# 40_Flash-eMMC_Flash.net
KiCad netlist of a schematic drawn in Altium Designer
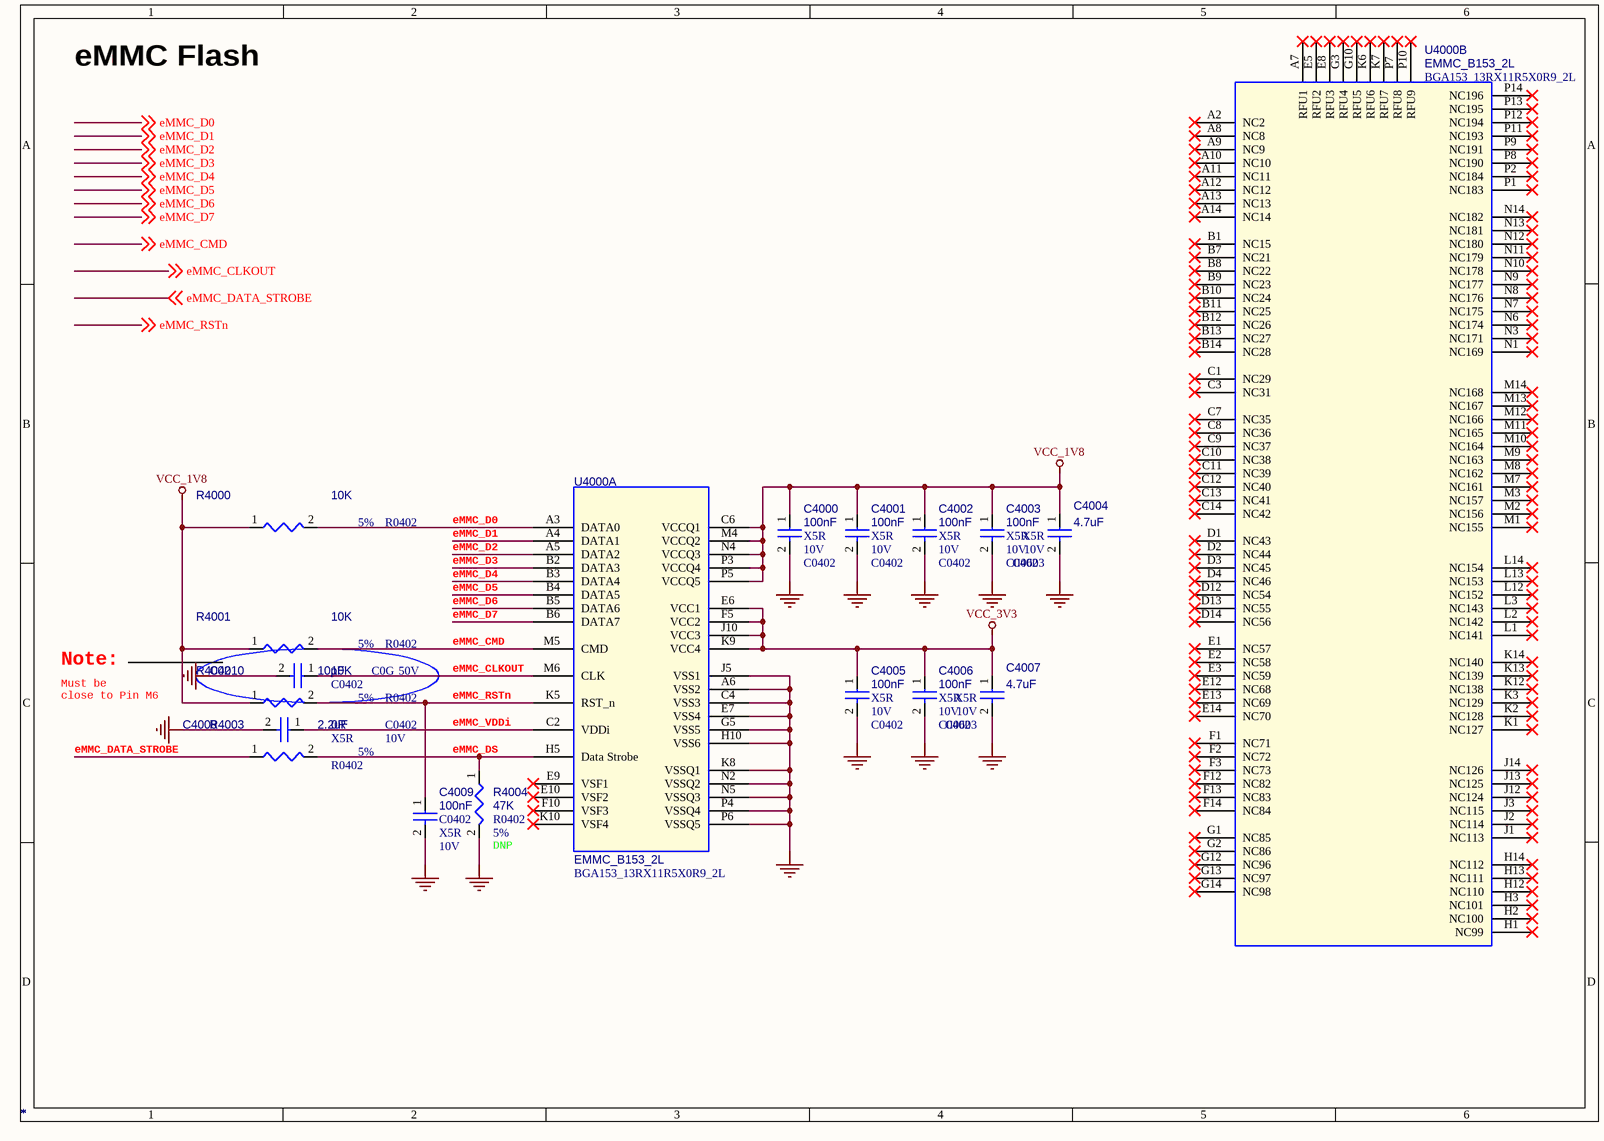
[diagram p0: 40.Flash-eMMC Flash.SchDoc]

(export (version "E")
  (design (tool "Eeschema 10.0.6"))
  (components
    (comp (ref "C4000")
      (value "*")
      (footprint "C0402")
      (description "cap,100.00nF,+/-10%,10V,X5R,C0402")
      (fields
        (field (name "VOLTAGE") "10V")
        (field (name "PCB FOOTPRINT") "C0402")
        (field (name "DIELECTRIC") "X5R")
        (field (name "TOLERANCE") "10%")
        (field (name "MANUFACTURER") "TDK")
        (field (name "ALTIUM_UNNAMED_1") "100nF")
        (field (name "CREATED BY") "JJJ")
      )
      (libsource (lib "*") (part "CAP NP"))
    )
    (comp (ref "C4001")
      (value "*")
      (footprint "C0402")
      (description "cap,100.00nF,+/-10%,10V,X5R,C0402")
      (fields
        (field (name "VOLTAGE") "10V")
        (field (name "PCB FOOTPRINT") "C0402")
        (field (name "DIELECTRIC") "X5R")
        (field (name "MANUFACTURER") "TDK")
        (field (name "TOLERANCE") "10%")
        (field (name "ALTIUM_UNNAMED_1") "100nF")
        (field (name "CREATED BY") "JJJ")
      )
      (libsource (lib "*") (part "CAP NP"))
    )
    (comp (ref "C4002")
      (value "*")
      (footprint "C0402")
      (description "cap,100.00nF,+/-10%,10V,X5R,C0402")
      (fields
        (field (name "VOLTAGE") "10V")
        (field (name "PCB FOOTPRINT") "C0402")
        (field (name "DIELECTRIC") "X5R")
        (field (name "MANUFACTURER") "TDK")
        (field (name "TOLERANCE") "10%")
        (field (name "ALTIUM_UNNAMED_1") "100nF")
        (field (name "CREATED BY") "JJJ")
      )
      (libsource (lib "*") (part "CAP NP"))
    )
    (comp (ref "C4003")
      (value "*")
      (footprint "C0402")
      (description "cap,100.00nF,+/-10%,10V,X5R,C0402")
      (fields
        (field (name "VOLTAGE") "10V")
        (field (name "PCB FOOTPRINT") "C0402")
        (field (name "DIELECTRIC") "X5R")
        (field (name "TOLERANCE") "10%")
        (field (name "MANUFACTURER") "TDK")
        (field (name "ALTIUM_UNNAMED_1") "100nF")
        (field (name "CREATED BY") "JJJ")
      )
      (libsource (lib "*") (part "CAP NP"))
    )
    (comp (ref "C4004")
      (value "*")
      (footprint "C0603")
      (description "cap,4.70uF,+/-10%,10V,X5R,C0603")
      (fields
        (field (name "VOLTAGE") "10V")
        (field (name "PCB FOOTPRINT") "C0603")
        (field (name "DIELECTRIC") "X5R")
        (field (name "TOLERANCE") "10%")
        (field (name "MANUFACTURER") "TDK")
        (field (name "ALTIUM_UNNAMED_1") "4.7uF")
        (field (name "CREATED BY") "JJJ")
      )
      (libsource (lib "*") (part "CAP NP"))
    )
    (comp (ref "C4005")
      (value "*")
      (footprint "C0402")
      (description "cap,100.00nF,+/-10%,10V,X5R,C0402")
      (fields
        (field (name "VOLTAGE") "10V")
        (field (name "PCB FOOTPRINT") "C0402")
        (field (name "DIELECTRIC") "X5R")
        (field (name "MANUFACTURER") "TDK")
        (field (name "TOLERANCE") "10%")
        (field (name "ALTIUM_UNNAMED_1") "100nF")
        (field (name "CREATED BY") "JJJ")
      )
      (libsource (lib "*") (part "CAP NP"))
    )
    (comp (ref "C4006")
      (value "*")
      (footprint "C0402")
      (description "cap,100.00nF,+/-10%,10V,X5R,C0402")
      (fields
        (field (name "VOLTAGE") "10V")
        (field (name "PCB FOOTPRINT") "C0402")
        (field (name "DIELECTRIC") "X5R")
        (field (name "MANUFACTURER") "TDK")
        (field (name "TOLERANCE") "10%")
        (field (name "ALTIUM_UNNAMED_1") "100nF")
        (field (name "CREATED BY") "JJJ")
      )
      (libsource (lib "*") (part "CAP NP"))
    )
    (comp (ref "C4007")
      (value "*")
      (footprint "C0603")
      (description "cap,4.70uF,+/-10%,10V,X5R,C0603")
      (fields
        (field (name "VOLTAGE") "10V")
        (field (name "PCB FOOTPRINT") "C0603")
        (field (name "DIELECTRIC") "X5R")
        (field (name "TOLERANCE") "10%")
        (field (name "MANUFACTURER") "TDK")
        (field (name "ALTIUM_UNNAMED_1") "4.7uF")
        (field (name "CREATED BY") "JJJ")
      )
      (libsource (lib "*") (part "CAP NP"))
    )
    (comp (ref "C4008")
      (value "*")
      (footprint "C0402")
      (description "cap,2.20uF,+/-10%,10V,X5R,C0402")
      (fields
        (field (name "VOLTAGE") "10V")
        (field (name "PCB FOOTPRINT") "C0402")
        (field (name "DIELECTRIC") "X5R")
        (field (name "TOLERANCE") "10%")
        (field (name "MANUFACTURER") "TDK")
        (field (name "ALTIUM_UNNAMED_1") "2.2uF")
        (field (name "CREATED BY") "JJJ")
      )
      (libsource (lib "*") (part "CAP NP"))
    )
    (comp (ref "C4009")
      (value "*")
      (footprint "C0402")
      (description "cap,100.00nF,+/-10%,10V,X5R,C0402")
      (fields
        (field (name "VOLTAGE") "10V")
        (field (name "PCB FOOTPRINT") "C0402")
        (field (name "DIELECTRIC") "X5R")
        (field (name "TOLERANCE") "10%")
        (field (name "MANUFACTURER") "TDK")
        (field (name "ALTIUM_UNNAMED_1") "100nF")
        (field (name "CREATED BY") "JJJ")
      )
      (libsource (lib "*") (part "CAP NP"))
    )
    (comp (ref "C4010")
      (value "*")
      (footprint "C0402")
      (description "cap,10.00pF,+/-0.5,50V,C0G,C0402")
      (fields
        (field (name "VOLTAGE") "50V")
        (field (name "PCB FOOTPRINT") "C0402")
        (field (name "DIELECTRIC") "C0G")
        (field (name "TOLERANCE") "+/-0.5pF")
        (field (name "MANUFACTURER") "TDK")
        (field (name "ALTIUM_UNNAMED_1") "10pF")
        (field (name "CREATED BY") "JJJ")
      )
      (libsource (lib "*") (part "CAP NP"))
    )
    (comp (ref "R4000")
      (value "*")
      (footprint "R0402")
      (description "НЁУГєсД¤µзЧи,10K,+/-5%,R0402,1/16W.")
      (fields
        (field (name "PCB FOOTPRINT") "R0402")
        (field (name "TOLERANCE") "5%")
        (field (name "MANUFACTURER") "YAGEO")
        (field (name "ALTIUM_UNNAMED_1") "10K")
        (field (name "CREATED BY") "YTL")
      )
      (libsource (lib "*") (part "RESISTOR_Dup1"))
    )
    (comp (ref "R4001")
      (value "*")
      (footprint "R0402")
      (description "НЁУГєсД¤µзЧи,10K,+/-5%,R0402,1/16W.")
      (fields
        (field (name "PCB FOOTPRINT") "R0402")
        (field (name "TOLERANCE") "5%")
        (field (name "MANUFACTURER") "YAGEO")
        (field (name "ALTIUM_UNNAMED_1") "10K")
        (field (name "CREATED BY") "YTL")
      )
      (libsource (lib "*") (part "RESISTOR_Dup1"))
    )
    (comp (ref "R4002")
      (value "*")
      (footprint "R0402")
      (description "НЁУГєсД¤µзЧи,10K,+/-5%,R0402,1/16W.")
      (fields
        (field (name "PCB FOOTPRINT") "R0402")
        (field (name "TOLERANCE") "5%")
        (field (name "MANUFACTURER") "YAGEO")
        (field (name "ALTIUM_UNNAMED_1") "10K")
        (field (name "CREATED BY") "YTL")
      )
      (libsource (lib "*") (part "RESISTOR_Dup1"))
    )
    (comp (ref "R4003")
      (value "*")
      (footprint "R0402")
      (description "НЁУГєсД¤µзЧи,0R,+/-5%,R0402,1/16W.")
      (fields
        (field (name "PCB FOOTPRINT") "R0402")
        (field (name "TOLERANCE") "5%")
        (field (name "MANUFACTURER") "YAGEO")
        (field (name "ALTIUM_UNNAMED_1") "0R")
        (field (name "CREATED BY") "YTL")
      )
      (libsource (lib "*") (part "RESISTOR_Dup1"))
    )
    (comp (ref "R4004")
      (value "*")
      (footprint "R0402")
      (description "НЁУГєсД¤µзЧи,47K,+/-5%,R0402,1/16W.")
      (fields
        (field (name "PCB FOOTPRINT") "R0402")
        (field (name "TOLERANCE") "5%")
        (field (name "MANUFACTURER") "YAGEO")
        (field (name "OPTION") "DNP")
        (field (name "ALTIUM_UNNAMED_1") "47K")
        (field (name "CREATED BY") "YTL")
      )
      (libsource (lib "*") (part "RESISTOR_Dup1"))
    )
    (comp (ref "U4000")
      (value "*")
      (footprint "BGA153_13RX11R5X0R9_2L")
      (description "EMMC_B153_2L,ёьєГµДВъЧг№¤ТХРиЗуЈ¬Fanout·ЅКЅІї·ЦЧЯПЯїзЅУФЩЗтО»ЙПЈ¬НЪіэA1\\C5ЗтО»")
      (fields
        (field (name "PCB FOOTPRINT") "BGA153_13RX11R5X0R9_2L")
        (field (name "ALTIUM_UNNAMED_1") "EMMC_B153_2L")
        (field (name "CREATED BY") "YWQ")
      )
      (libsource (lib "*") (part "INAND_EMMC_153_2L"))
    )
  )
  (nets
    (net (code "1") (name "/eMMC_DS") (class "Default")
      (node (ref "R4003") (pin "2") (pinfunction "2_2") (pintype "passive"))
      (node (ref "R4004") (pin "1") (pinfunction "1_1") (pintype "passive"))
      (node (ref "U4000") (pin "H5") (pinfunction "Data_Strobe_H5") (pintype "passive"))
    )
    (net (code "2") (name "/eMMC_VDDi") (class "Default")
      (node (ref "C4008") (pin "1") (pinfunction "1_1") (pintype "passive"))
      (node (ref "U4000") (pin "C2") (pinfunction "VDDi_C2") (pintype "passive"))
    )
    (net (code "3") (name "GND") (class "Default")
      (node (ref "C4000") (pin "2") (pinfunction "2_2") (pintype "passive"))
      (node (ref "C4001") (pin "2") (pinfunction "2_2") (pintype "passive"))
      (node (ref "C4002") (pin "2") (pinfunction "2_2") (pintype "passive"))
      (node (ref "C4003") (pin "2") (pinfunction "2_2") (pintype "passive"))
      (node (ref "C4004") (pin "2") (pinfunction "2_2") (pintype "passive"))
      (node (ref "C4005") (pin "2") (pinfunction "2_2") (pintype "passive"))
      (node (ref "C4006") (pin "2") (pinfunction "2_2") (pintype "passive"))
      (node (ref "C4007") (pin "2") (pinfunction "2_2") (pintype "passive"))
      (node (ref "C4008") (pin "2") (pinfunction "2_2") (pintype "passive"))
      (node (ref "C4009") (pin "2") (pinfunction "2_2") (pintype "passive"))
      (node (ref "C4010") (pin "2") (pinfunction "2_2") (pintype "passive"))
      (node (ref "R4004") (pin "2") (pinfunction "2_2") (pintype "passive"))
      (node (ref "U4000") (pin "A6") (pinfunction "VSS2_A6") (pintype "passive"))
      (node (ref "U4000") (pin "C4") (pinfunction "VSS3_C4") (pintype "passive"))
      (node (ref "U4000") (pin "E7") (pinfunction "VSS4_E7") (pintype "passive"))
      (node (ref "U4000") (pin "G5") (pinfunction "VSS5_G5") (pintype "passive"))
      (node (ref "U4000") (pin "H10") (pinfunction "VSS6_H10") (pintype "passive"))
      (node (ref "U4000") (pin "J5") (pinfunction "VSS1_J5") (pintype "passive"))
      (node (ref "U4000") (pin "K8") (pinfunction "VSSQ1_K8") (pintype "passive"))
      (node (ref "U4000") (pin "N2") (pinfunction "VSSQ2_N2") (pintype "passive"))
      (node (ref "U4000") (pin "N5") (pinfunction "VSSQ3_N5") (pintype "passive"))
      (node (ref "U4000") (pin "P4") (pinfunction "VSSQ4_P4") (pintype "passive"))
      (node (ref "U4000") (pin "P6") (pinfunction "VSSQ5_P6") (pintype "passive"))
    )
    (net (code "4") (name "VCC_1V8") (class "Default")
      (node (ref "C4000") (pin "1") (pinfunction "1_1") (pintype "passive"))
      (node (ref "C4001") (pin "1") (pinfunction "1_1") (pintype "passive"))
      (node (ref "C4002") (pin "1") (pinfunction "1_1") (pintype "passive"))
      (node (ref "C4003") (pin "1") (pinfunction "1_1") (pintype "passive"))
      (node (ref "C4004") (pin "1") (pinfunction "1_1") (pintype "passive"))
      (node (ref "R4000") (pin "1") (pinfunction "1_1") (pintype "passive"))
      (node (ref "R4001") (pin "1") (pinfunction "1_1") (pintype "passive"))
      (node (ref "R4002") (pin "1") (pinfunction "1_1") (pintype "passive"))
      (node (ref "U4000") (pin "C6") (pinfunction "VCCQ1_C6") (pintype "passive"))
      (node (ref "U4000") (pin "M4") (pinfunction "VCCQ2_M4") (pintype "passive"))
      (node (ref "U4000") (pin "N4") (pinfunction "VCCQ3_N4") (pintype "passive"))
      (node (ref "U4000") (pin "P3") (pinfunction "VCCQ4_P3") (pintype "passive"))
      (node (ref "U4000") (pin "P5") (pinfunction "VCCQ5_P5") (pintype "passive"))
    )
    (net (code "5") (name "VCC_3V3") (class "Default")
      (node (ref "C4005") (pin "1") (pinfunction "1_1") (pintype "passive"))
      (node (ref "C4006") (pin "1") (pinfunction "1_1") (pintype "passive"))
      (node (ref "C4007") (pin "1") (pinfunction "1_1") (pintype "passive"))
      (node (ref "U4000") (pin "E6") (pinfunction "VCC1_E6") (pintype "passive"))
      (node (ref "U4000") (pin "F5") (pinfunction "VCC2_F5") (pintype "passive"))
      (node (ref "U4000") (pin "J10") (pinfunction "VCC3_J10") (pintype "passive"))
      (node (ref "U4000") (pin "K9") (pinfunction "VCC4_K9") (pintype "passive"))
    )
    (net (code "6") (name "eMMC_CLKOUT") (class "Default")
      (node (ref "C4010") (pin "1") (pinfunction "1_1") (pintype "passive"))
      (node (ref "U4000") (pin "M6") (pinfunction "CLK_M6") (pintype "passive"))
    )
    (net (code "7") (name "eMMC_CMD") (class "Default")
      (node (ref "R4001") (pin "2") (pinfunction "2_2") (pintype "passive"))
      (node (ref "U4000") (pin "M5") (pinfunction "CMD_M5") (pintype "passive"))
    )
    (net (code "8") (name "eMMC_D0") (class "Default")
      (node (ref "R4000") (pin "2") (pinfunction "2_2") (pintype "passive"))
      (node (ref "U4000") (pin "A3") (pinfunction "DATA0_A3") (pintype "passive"))
    )
    (net (code "9") (name "eMMC_D1") (class "Default")
      (node (ref "U4000") (pin "A4") (pinfunction "DATA1_A4") (pintype "passive"))
    )
    (net (code "10") (name "eMMC_D2") (class "Default")
      (node (ref "U4000") (pin "A5") (pinfunction "DATA2_A5") (pintype "passive"))
    )
    (net (code "11") (name "eMMC_D3") (class "Default")
      (node (ref "U4000") (pin "B2") (pinfunction "DATA3_B2") (pintype "passive"))
    )
    (net (code "12") (name "eMMC_D4") (class "Default")
      (node (ref "U4000") (pin "B3") (pinfunction "DATA4_B3") (pintype "passive"))
    )
    (net (code "13") (name "eMMC_D5") (class "Default")
      (node (ref "U4000") (pin "B4") (pinfunction "DATA5_B4") (pintype "passive"))
    )
    (net (code "14") (name "eMMC_D6") (class "Default")
      (node (ref "U4000") (pin "B5") (pinfunction "DATA6_B5") (pintype "passive"))
    )
    (net (code "15") (name "eMMC_D7") (class "Default")
      (node (ref "U4000") (pin "B6") (pinfunction "DATA7_B6") (pintype "passive"))
    )
    (net (code "16") (name "eMMC_DATA_STROBE") (class "Default")
      (node (ref "R4003") (pin "1") (pinfunction "1_1") (pintype "passive"))
    )
    (net (code "17") (name "eMMC_RSTn") (class "Default")
      (node (ref "C4009") (pin "1") (pinfunction "1_1") (pintype "passive"))
      (node (ref "R4002") (pin "2") (pinfunction "2_2") (pintype "passive"))
      (node (ref "U4000") (pin "K5") (pinfunction "RST_n_K5") (pintype "passive"))
    )
    (net (code "18") (name "unconnected-(U4000A-VSF1-PadE9)") (class "Default")
      (node (ref "U4000") (pin "E9") (pinfunction "VSF1_E9") (pintype "passive+no_connect"))
    )
    (net (code "19") (name "unconnected-(U4000A-VSF2-PadE10)") (class "Default")
      (node (ref "U4000") (pin "E10") (pinfunction "VSF2_E10") (pintype "passive+no_connect"))
    )
    (net (code "20") (name "unconnected-(U4000A-VSF3-PadF10)") (class "Default")
      (node (ref "U4000") (pin "F10") (pinfunction "VSF3_F10") (pintype "passive+no_connect"))
    )
    (net (code "21") (name "unconnected-(U4000A-VSF4-PadK10)") (class "Default")
      (node (ref "U4000") (pin "K10") (pinfunction "VSF4_K10") (pintype "passive+no_connect"))
    )
    (net (code "22") (name "unconnected-(U4000B-NC2-PadA2)") (class "Default")
      (node (ref "U4000") (pin "A2") (pinfunction "NC2_A2") (pintype "passive+no_connect"))
    )
    (net (code "23") (name "unconnected-(U4000B-NC8-PadA8)") (class "Default")
      (node (ref "U4000") (pin "A8") (pinfunction "NC8_A8") (pintype "passive+no_connect"))
    )
    (net (code "24") (name "unconnected-(U4000B-NC9-PadA9)") (class "Default")
      (node (ref "U4000") (pin "A9") (pinfunction "NC9_A9") (pintype "passive+no_connect"))
    )
    (net (code "25") (name "unconnected-(U4000B-NC10-PadA10)") (class "Default")
      (node (ref "U4000") (pin "A10") (pinfunction "NC10_A10") (pintype "passive+no_connect"))
    )
    (net (code "26") (name "unconnected-(U4000B-NC11-PadA11)") (class "Default")
      (node (ref "U4000") (pin "A11") (pinfunction "NC11_A11") (pintype "passive+no_connect"))
    )
    (net (code "27") (name "unconnected-(U4000B-NC12-PadA12)") (class "Default")
      (node (ref "U4000") (pin "A12") (pinfunction "NC12_A12") (pintype "passive+no_connect"))
    )
    (net (code "28") (name "unconnected-(U4000B-NC13-PadA13)") (class "Default")
      (node (ref "U4000") (pin "A13") (pinfunction "NC13_A13") (pintype "passive+no_connect"))
    )
    (net (code "29") (name "unconnected-(U4000B-NC14-PadA14)") (class "Default")
      (node (ref "U4000") (pin "A14") (pinfunction "NC14_A14") (pintype "passive+no_connect"))
    )
    (net (code "30") (name "unconnected-(U4000B-NC15-PadB1)") (class "Default")
      (node (ref "U4000") (pin "B1") (pinfunction "NC15_B1") (pintype "passive+no_connect"))
    )
    (net (code "31") (name "unconnected-(U4000B-NC21-PadB7)") (class "Default")
      (node (ref "U4000") (pin "B7") (pinfunction "NC21_B7") (pintype "passive+no_connect"))
    )
    (net (code "32") (name "unconnected-(U4000B-NC22-PadB8)") (class "Default")
      (node (ref "U4000") (pin "B8") (pinfunction "NC22_B8") (pintype "passive+no_connect"))
    )
    (net (code "33") (name "unconnected-(U4000B-NC23-PadB9)") (class "Default")
      (node (ref "U4000") (pin "B9") (pinfunction "NC23_B9") (pintype "passive+no_connect"))
    )
    (net (code "34") (name "unconnected-(U4000B-NC24-PadB10)") (class "Default")
      (node (ref "U4000") (pin "B10") (pinfunction "NC24_B10") (pintype "passive+no_connect"))
    )
    (net (code "35") (name "unconnected-(U4000B-NC25-PadB11)") (class "Default")
      (node (ref "U4000") (pin "B11") (pinfunction "NC25_B11") (pintype "passive+no_connect"))
    )
    (net (code "36") (name "unconnected-(U4000B-NC26-PadB12)") (class "Default")
      (node (ref "U4000") (pin "B12") (pinfunction "NC26_B12") (pintype "passive+no_connect"))
    )
    (net (code "37") (name "unconnected-(U4000B-NC27-PadB13)") (class "Default")
      (node (ref "U4000") (pin "B13") (pinfunction "NC27_B13") (pintype "passive+no_connect"))
    )
    (net (code "38") (name "unconnected-(U4000B-NC28-PadB14)") (class "Default")
      (node (ref "U4000") (pin "B14") (pinfunction "NC28_B14") (pintype "passive+no_connect"))
    )
    (net (code "39") (name "unconnected-(U4000B-NC29-PadC1)") (class "Default")
      (node (ref "U4000") (pin "C1") (pinfunction "NC29_C1") (pintype "passive+no_connect"))
    )
    (net (code "40") (name "unconnected-(U4000B-NC31-PadC3)") (class "Default")
      (node (ref "U4000") (pin "C3") (pinfunction "NC31_C3") (pintype "passive+no_connect"))
    )
    (net (code "41") (name "unconnected-(U4000B-NC35-PadC7)") (class "Default")
      (node (ref "U4000") (pin "C7") (pinfunction "NC35_C7") (pintype "passive+no_connect"))
    )
    (net (code "42") (name "unconnected-(U4000B-NC36-PadC8)") (class "Default")
      (node (ref "U4000") (pin "C8") (pinfunction "NC36_C8") (pintype "passive+no_connect"))
    )
    (net (code "43") (name "unconnected-(U4000B-NC37-PadC9)") (class "Default")
      (node (ref "U4000") (pin "C9") (pinfunction "NC37_C9") (pintype "passive+no_connect"))
    )
    (net (code "44") (name "unconnected-(U4000B-NC38-PadC10)") (class "Default")
      (node (ref "U4000") (pin "C10") (pinfunction "NC38_C10") (pintype "passive+no_connect"))
    )
    (net (code "45") (name "unconnected-(U4000B-NC39-PadC11)") (class "Default")
      (node (ref "U4000") (pin "C11") (pinfunction "NC39_C11") (pintype "passive+no_connect"))
    )
    (net (code "46") (name "unconnected-(U4000B-NC40-PadC12)") (class "Default")
      (node (ref "U4000") (pin "C12") (pinfunction "NC40_C12") (pintype "passive+no_connect"))
    )
    (net (code "47") (name "unconnected-(U4000B-NC41-PadC13)") (class "Default")
      (node (ref "U4000") (pin "C13") (pinfunction "NC41_C13") (pintype "passive+no_connect"))
    )
    (net (code "48") (name "unconnected-(U4000B-NC42-PadC14)") (class "Default")
      (node (ref "U4000") (pin "C14") (pinfunction "NC42_C14") (pintype "passive+no_connect"))
    )
    (net (code "49") (name "unconnected-(U4000B-NC43-PadD1)") (class "Default")
      (node (ref "U4000") (pin "D1") (pinfunction "NC43_D1") (pintype "passive+no_connect"))
    )
    (net (code "50") (name "unconnected-(U4000B-NC44-PadD2)") (class "Default")
      (node (ref "U4000") (pin "D2") (pinfunction "NC44_D2") (pintype "passive+no_connect"))
    )
    (net (code "51") (name "unconnected-(U4000B-NC45-PadD3)") (class "Default")
      (node (ref "U4000") (pin "D3") (pinfunction "NC45_D3") (pintype "passive+no_connect"))
    )
    (net (code "52") (name "unconnected-(U4000B-NC46-PadD4)") (class "Default")
      (node (ref "U4000") (pin "D4") (pinfunction "NC46_D4") (pintype "passive+no_connect"))
    )
    (net (code "53") (name "unconnected-(U4000B-NC54-PadD12)") (class "Default")
      (node (ref "U4000") (pin "D12") (pinfunction "NC54_D12") (pintype "passive+no_connect"))
    )
    (net (code "54") (name "unconnected-(U4000B-NC55-PadD13)") (class "Default")
      (node (ref "U4000") (pin "D13") (pinfunction "NC55_D13") (pintype "passive+no_connect"))
    )
    (net (code "55") (name "unconnected-(U4000B-NC56-PadD14)") (class "Default")
      (node (ref "U4000") (pin "D14") (pinfunction "NC56_D14") (pintype "passive+no_connect"))
    )
    (net (code "56") (name "unconnected-(U4000B-NC57-PadE1)") (class "Default")
      (node (ref "U4000") (pin "E1") (pinfunction "NC57_E1") (pintype "passive+no_connect"))
    )
    (net (code "57") (name "unconnected-(U4000B-NC58-PadE2)") (class "Default")
      (node (ref "U4000") (pin "E2") (pinfunction "NC58_E2") (pintype "passive+no_connect"))
    )
    (net (code "58") (name "unconnected-(U4000B-NC59-PadE3)") (class "Default")
      (node (ref "U4000") (pin "E3") (pinfunction "NC59_E3") (pintype "passive+no_connect"))
    )
    (net (code "59") (name "unconnected-(U4000B-NC68-PadE12)") (class "Default")
      (node (ref "U4000") (pin "E12") (pinfunction "NC68_E12") (pintype "passive+no_connect"))
    )
    (net (code "60") (name "unconnected-(U4000B-NC69-PadE13)") (class "Default")
      (node (ref "U4000") (pin "E13") (pinfunction "NC69_E13") (pintype "passive+no_connect"))
    )
    (net (code "61") (name "unconnected-(U4000B-NC70-PadE14)") (class "Default")
      (node (ref "U4000") (pin "E14") (pinfunction "NC70_E14") (pintype "passive+no_connect"))
    )
    (net (code "62") (name "unconnected-(U4000B-NC71-PadF1)") (class "Default")
      (node (ref "U4000") (pin "F1") (pinfunction "NC71_F1") (pintype "passive+no_connect"))
    )
    (net (code "63") (name "unconnected-(U4000B-NC72-PadF2)") (class "Default")
      (node (ref "U4000") (pin "F2") (pinfunction "NC72_F2") (pintype "passive+no_connect"))
    )
    (net (code "64") (name "unconnected-(U4000B-NC73-PadF3)") (class "Default")
      (node (ref "U4000") (pin "F3") (pinfunction "NC73_F3") (pintype "passive+no_connect"))
    )
    (net (code "65") (name "unconnected-(U4000B-NC82-PadF12)") (class "Default")
      (node (ref "U4000") (pin "F12") (pinfunction "NC82_F12") (pintype "passive+no_connect"))
    )
    (net (code "66") (name "unconnected-(U4000B-NC83-PadF13)") (class "Default")
      (node (ref "U4000") (pin "F13") (pinfunction "NC83_F13") (pintype "passive+no_connect"))
    )
    (net (code "67") (name "unconnected-(U4000B-NC84-PadF14)") (class "Default")
      (node (ref "U4000") (pin "F14") (pinfunction "NC84_F14") (pintype "passive+no_connect"))
    )
    (net (code "68") (name "unconnected-(U4000B-NC85-PadG1)") (class "Default")
      (node (ref "U4000") (pin "G1") (pinfunction "NC85_G1") (pintype "passive+no_connect"))
    )
    (net (code "69") (name "unconnected-(U4000B-NC86-PadG2)") (class "Default")
      (node (ref "U4000") (pin "G2") (pinfunction "NC86_G2") (pintype "passive+no_connect"))
    )
    (net (code "70") (name "unconnected-(U4000B-NC96-PadG12)") (class "Default")
      (node (ref "U4000") (pin "G12") (pinfunction "NC96_G12") (pintype "passive+no_connect"))
    )
    (net (code "71") (name "unconnected-(U4000B-NC97-PadG13)") (class "Default")
      (node (ref "U4000") (pin "G13") (pinfunction "NC97_G13") (pintype "passive+no_connect"))
    )
    (net (code "72") (name "unconnected-(U4000B-NC98-PadG14)") (class "Default")
      (node (ref "U4000") (pin "G14") (pinfunction "NC98_G14") (pintype "passive+no_connect"))
    )
    (net (code "73") (name "unconnected-(U4000B-NC99-PadH1)") (class "Default")
      (node (ref "U4000") (pin "H1") (pinfunction "NC99_H1") (pintype "passive+no_connect"))
    )
    (net (code "74") (name "unconnected-(U4000B-NC100-PadH2)") (class "Default")
      (node (ref "U4000") (pin "H2") (pinfunction "NC100_H2") (pintype "passive+no_connect"))
    )
    (net (code "75") (name "unconnected-(U4000B-NC101-PadH3)") (class "Default")
      (node (ref "U4000") (pin "H3") (pinfunction "NC101_H3") (pintype "passive+no_connect"))
    )
    (net (code "76") (name "unconnected-(U4000B-NC110-PadH12)") (class "Default")
      (node (ref "U4000") (pin "H12") (pinfunction "NC110_H12") (pintype "passive+no_connect"))
    )
    (net (code "77") (name "unconnected-(U4000B-NC111-PadH13)") (class "Default")
      (node (ref "U4000") (pin "H13") (pinfunction "NC111_H13") (pintype "passive+no_connect"))
    )
    (net (code "78") (name "unconnected-(U4000B-NC112-PadH14)") (class "Default")
      (node (ref "U4000") (pin "H14") (pinfunction "NC112_H14") (pintype "passive+no_connect"))
    )
    (net (code "79") (name "unconnected-(U4000B-NC113-PadJ1)") (class "Default")
      (node (ref "U4000") (pin "J1") (pinfunction "NC113_J1") (pintype "passive+no_connect"))
    )
    (net (code "80") (name "unconnected-(U4000B-NC114-PadJ2)") (class "Default")
      (node (ref "U4000") (pin "J2") (pinfunction "NC114_J2") (pintype "passive+no_connect"))
    )
    (net (code "81") (name "unconnected-(U4000B-NC115-PadJ3)") (class "Default")
      (node (ref "U4000") (pin "J3") (pinfunction "NC115_J3") (pintype "passive+no_connect"))
    )
    (net (code "82") (name "unconnected-(U4000B-NC124-PadJ12)") (class "Default")
      (node (ref "U4000") (pin "J12") (pinfunction "NC124_J12") (pintype "passive+no_connect"))
    )
    (net (code "83") (name "unconnected-(U4000B-NC125-PadJ13)") (class "Default")
      (node (ref "U4000") (pin "J13") (pinfunction "NC125_J13") (pintype "passive+no_connect"))
    )
    (net (code "84") (name "unconnected-(U4000B-NC126-PadJ14)") (class "Default")
      (node (ref "U4000") (pin "J14") (pinfunction "NC126_J14") (pintype "passive+no_connect"))
    )
    (net (code "85") (name "unconnected-(U4000B-NC127-PadK1)") (class "Default")
      (node (ref "U4000") (pin "K1") (pinfunction "NC127_K1") (pintype "passive+no_connect"))
    )
    (net (code "86") (name "unconnected-(U4000B-NC128-PadK2)") (class "Default")
      (node (ref "U4000") (pin "K2") (pinfunction "NC128_K2") (pintype "passive+no_connect"))
    )
    (net (code "87") (name "unconnected-(U4000B-NC129-PadK3)") (class "Default")
      (node (ref "U4000") (pin "K3") (pinfunction "NC129_K3") (pintype "passive+no_connect"))
    )
    (net (code "88") (name "unconnected-(U4000B-NC138-PadK12)") (class "Default")
      (node (ref "U4000") (pin "K12") (pinfunction "NC138_K12") (pintype "passive+no_connect"))
    )
    (net (code "89") (name "unconnected-(U4000B-NC139-PadK13)") (class "Default")
      (node (ref "U4000") (pin "K13") (pinfunction "NC139_K13") (pintype "passive+no_connect"))
    )
    (net (code "90") (name "unconnected-(U4000B-NC140-PadK14)") (class "Default")
      (node (ref "U4000") (pin "K14") (pinfunction "NC140_K14") (pintype "passive+no_connect"))
    )
    (net (code "91") (name "unconnected-(U4000B-NC141-PadL1)") (class "Default")
      (node (ref "U4000") (pin "L1") (pinfunction "NC141_L1") (pintype "passive+no_connect"))
    )
    (net (code "92") (name "unconnected-(U4000B-NC142-PadL2)") (class "Default")
      (node (ref "U4000") (pin "L2") (pinfunction "NC142_L2") (pintype "passive+no_connect"))
    )
    (net (code "93") (name "unconnected-(U4000B-NC143-PadL3)") (class "Default")
      (node (ref "U4000") (pin "L3") (pinfunction "NC143_L3") (pintype "passive+no_connect"))
    )
    (net (code "94") (name "unconnected-(U4000B-NC152-PadL12)") (class "Default")
      (node (ref "U4000") (pin "L12") (pinfunction "NC152_L12") (pintype "passive+no_connect"))
    )
    (net (code "95") (name "unconnected-(U4000B-NC153-PadL13)") (class "Default")
      (node (ref "U4000") (pin "L13") (pinfunction "NC153_L13") (pintype "passive+no_connect"))
    )
    (net (code "96") (name "unconnected-(U4000B-NC154-PadL14)") (class "Default")
      (node (ref "U4000") (pin "L14") (pinfunction "NC154_L14") (pintype "passive+no_connect"))
    )
    (net (code "97") (name "unconnected-(U4000B-NC155-PadM1)") (class "Default")
      (node (ref "U4000") (pin "M1") (pinfunction "NC155_M1") (pintype "passive+no_connect"))
    )
    (net (code "98") (name "unconnected-(U4000B-NC156-PadM2)") (class "Default")
      (node (ref "U4000") (pin "M2") (pinfunction "NC156_M2") (pintype "passive+no_connect"))
    )
    (net (code "99") (name "unconnected-(U4000B-NC157-PadM3)") (class "Default")
      (node (ref "U4000") (pin "M3") (pinfunction "NC157_M3") (pintype "passive+no_connect"))
    )
    (net (code "100") (name "unconnected-(U4000B-NC161-PadM7)") (class "Default")
      (node (ref "U4000") (pin "M7") (pinfunction "NC161_M7") (pintype "passive+no_connect"))
    )
    (net (code "101") (name "unconnected-(U4000B-NC162-PadM8)") (class "Default")
      (node (ref "U4000") (pin "M8") (pinfunction "NC162_M8") (pintype "passive+no_connect"))
    )
    (net (code "102") (name "unconnected-(U4000B-NC163-PadM9)") (class "Default")
      (node (ref "U4000") (pin "M9") (pinfunction "NC163_M9") (pintype "passive+no_connect"))
    )
    (net (code "103") (name "unconnected-(U4000B-NC164-PadM10)") (class "Default")
      (node (ref "U4000") (pin "M10") (pinfunction "NC164_M10") (pintype "passive+no_connect"))
    )
    (net (code "104") (name "unconnected-(U4000B-NC165-PadM11)") (class "Default")
      (node (ref "U4000") (pin "M11") (pinfunction "NC165_M11") (pintype "passive+no_connect"))
    )
    (net (code "105") (name "unconnected-(U4000B-NC166-PadM12)") (class "Default")
      (node (ref "U4000") (pin "M12") (pinfunction "NC166_M12") (pintype "passive+no_connect"))
    )
    (net (code "106") (name "unconnected-(U4000B-NC167-PadM13)") (class "Default")
      (node (ref "U4000") (pin "M13") (pinfunction "NC167_M13") (pintype "passive+no_connect"))
    )
    (net (code "107") (name "unconnected-(U4000B-NC168-PadM14)") (class "Default")
      (node (ref "U4000") (pin "M14") (pinfunction "NC168_M14") (pintype "passive+no_connect"))
    )
    (net (code "108") (name "unconnected-(U4000B-NC169-PadN1)") (class "Default")
      (node (ref "U4000") (pin "N1") (pinfunction "NC169_N1") (pintype "passive+no_connect"))
    )
    (net (code "109") (name "unconnected-(U4000B-NC171-PadN3)") (class "Default")
      (node (ref "U4000") (pin "N3") (pinfunction "NC171_N3") (pintype "passive+no_connect"))
    )
    (net (code "110") (name "unconnected-(U4000B-NC174-PadN6)") (class "Default")
      (node (ref "U4000") (pin "N6") (pinfunction "NC174_N6") (pintype "passive+no_connect"))
    )
    (net (code "111") (name "unconnected-(U4000B-NC175-PadN7)") (class "Default")
      (node (ref "U4000") (pin "N7") (pinfunction "NC175_N7") (pintype "passive+no_connect"))
    )
    (net (code "112") (name "unconnected-(U4000B-NC176-PadN8)") (class "Default")
      (node (ref "U4000") (pin "N8") (pinfunction "NC176_N8") (pintype "passive+no_connect"))
    )
    (net (code "113") (name "unconnected-(U4000B-NC177-PadN9)") (class "Default")
      (node (ref "U4000") (pin "N9") (pinfunction "NC177_N9") (pintype "passive+no_connect"))
    )
    (net (code "114") (name "unconnected-(U4000B-NC178-PadN10)") (class "Default")
      (node (ref "U4000") (pin "N10") (pinfunction "NC178_N10") (pintype "passive+no_connect"))
    )
    (net (code "115") (name "unconnected-(U4000B-NC179-PadN11)") (class "Default")
      (node (ref "U4000") (pin "N11") (pinfunction "NC179_N11") (pintype "passive+no_connect"))
    )
    (net (code "116") (name "unconnected-(U4000B-NC180-PadN12)") (class "Default")
      (node (ref "U4000") (pin "N12") (pinfunction "NC180_N12") (pintype "passive+no_connect"))
    )
    (net (code "117") (name "unconnected-(U4000B-NC181-PadN13)") (class "Default")
      (node (ref "U4000") (pin "N13") (pinfunction "NC181_N13") (pintype "passive+no_connect"))
    )
    (net (code "118") (name "unconnected-(U4000B-NC182-PadN14)") (class "Default")
      (node (ref "U4000") (pin "N14") (pinfunction "NC182_N14") (pintype "passive+no_connect"))
    )
    (net (code "119") (name "unconnected-(U4000B-NC183-PadP1)") (class "Default")
      (node (ref "U4000") (pin "P1") (pinfunction "NC183_P1") (pintype "passive+no_connect"))
    )
    (net (code "120") (name "unconnected-(U4000B-NC184-PadP2)") (class "Default")
      (node (ref "U4000") (pin "P2") (pinfunction "NC184_P2") (pintype "passive+no_connect"))
    )
    (net (code "121") (name "unconnected-(U4000B-NC190-PadP8)") (class "Default")
      (node (ref "U4000") (pin "P8") (pinfunction "NC190_P8") (pintype "passive+no_connect"))
    )
    (net (code "122") (name "unconnected-(U4000B-NC191-PadP9)") (class "Default")
      (node (ref "U4000") (pin "P9") (pinfunction "NC191_P9") (pintype "passive+no_connect"))
    )
    (net (code "123") (name "unconnected-(U4000B-NC193-PadP11)") (class "Default")
      (node (ref "U4000") (pin "P11") (pinfunction "NC193_P11") (pintype "passive+no_connect"))
    )
    (net (code "124") (name "unconnected-(U4000B-NC194-PadP12)") (class "Default")
      (node (ref "U4000") (pin "P12") (pinfunction "NC194_P12") (pintype "passive+no_connect"))
    )
    (net (code "125") (name "unconnected-(U4000B-NC195-PadP13)") (class "Default")
      (node (ref "U4000") (pin "P13") (pinfunction "NC195_P13") (pintype "passive+no_connect"))
    )
    (net (code "126") (name "unconnected-(U4000B-NC196-PadP14)") (class "Default")
      (node (ref "U4000") (pin "P14") (pinfunction "NC196_P14") (pintype "passive+no_connect"))
    )
    (net (code "127") (name "unconnected-(U4000B-RFU1-PadA7)") (class "Default")
      (node (ref "U4000") (pin "A7") (pinfunction "RFU1_A7") (pintype "passive+no_connect"))
    )
    (net (code "128") (name "unconnected-(U4000B-RFU2-PadE5)") (class "Default")
      (node (ref "U4000") (pin "E5") (pinfunction "RFU2_E5") (pintype "passive+no_connect"))
    )
    (net (code "129") (name "unconnected-(U4000B-RFU3-PadE8)") (class "Default")
      (node (ref "U4000") (pin "E8") (pinfunction "RFU3_E8") (pintype "passive+no_connect"))
    )
    (net (code "130") (name "unconnected-(U4000B-RFU4-PadG3)") (class "Default")
      (node (ref "U4000") (pin "G3") (pinfunction "RFU4_G3") (pintype "passive+no_connect"))
    )
    (net (code "131") (name "unconnected-(U4000B-RFU5-PadG10)") (class "Default")
      (node (ref "U4000") (pin "G10") (pinfunction "RFU5_G10") (pintype "passive+no_connect"))
    )
    (net (code "132") (name "unconnected-(U4000B-RFU6-PadK6)") (class "Default")
      (node (ref "U4000") (pin "K6") (pinfunction "RFU6_K6") (pintype "passive+no_connect"))
    )
    (net (code "133") (name "unconnected-(U4000B-RFU7-PadK7)") (class "Default")
      (node (ref "U4000") (pin "K7") (pinfunction "RFU7_K7") (pintype "passive+no_connect"))
    )
    (net (code "134") (name "unconnected-(U4000B-RFU8-PadP7)") (class "Default")
      (node (ref "U4000") (pin "P7") (pinfunction "RFU8_P7") (pintype "passive+no_connect"))
    )
    (net (code "135") (name "unconnected-(U4000B-RFU9-PadP10)") (class "Default")
      (node (ref "U4000") (pin "P10") (pinfunction "RFU9_P10") (pintype "passive+no_connect"))
    )
  )
)
